# MDM_V3_ControlBoard_A.net
KiCad netlist of a schematic drawn in EAGLE
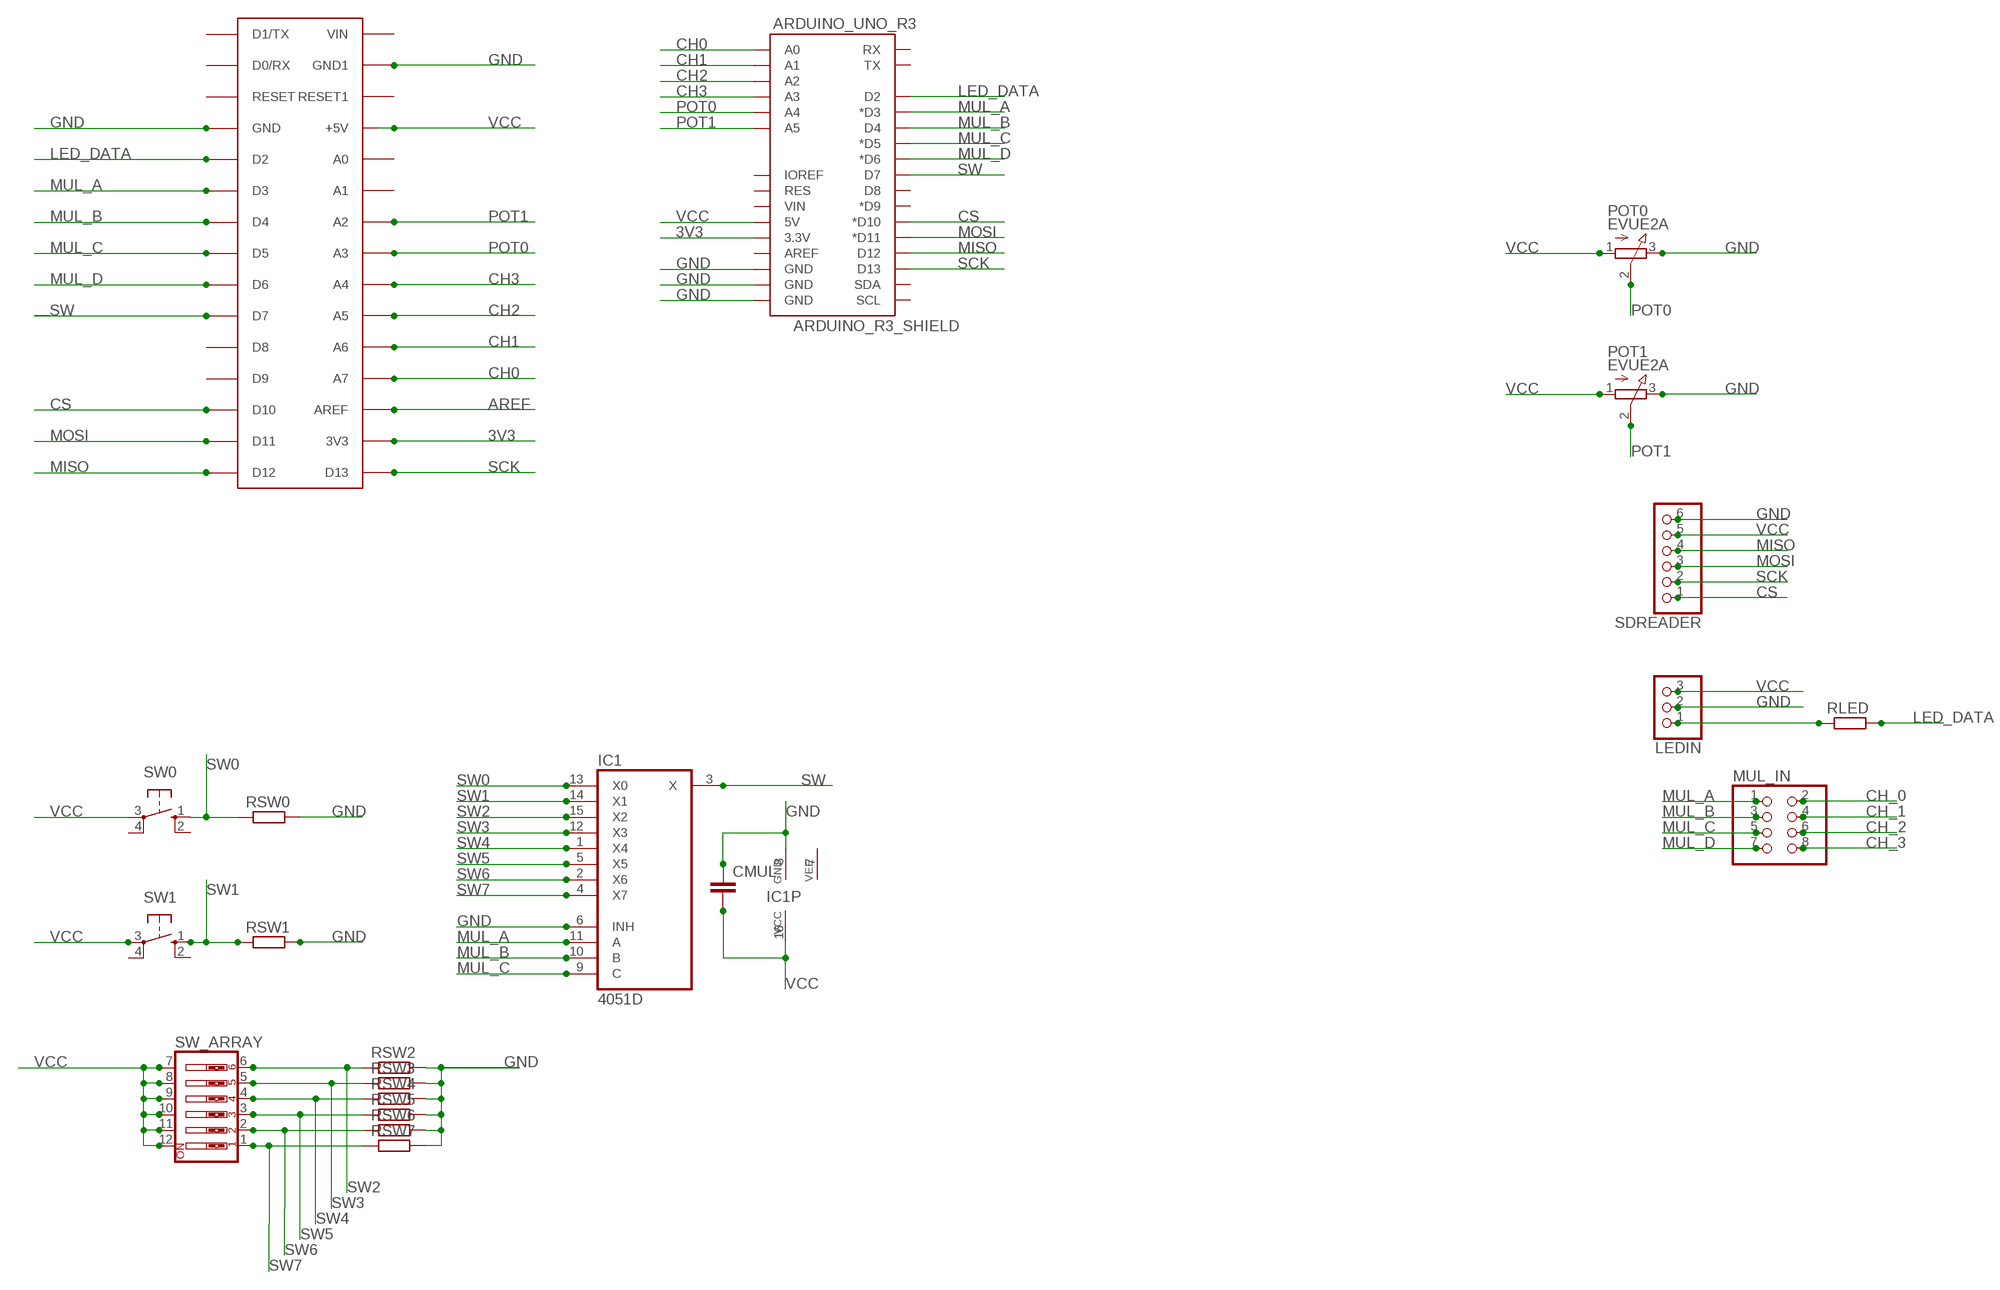
[diagram p0: schematic, sheet 1]

(export (version "E")
  (design (tool "Eeschema 10.0.6"))
  (components
    (comp (ref "ARDUINO_NANO")
      (value "ARDUINONANO")
      (footprint "eagle-import:PDIP-32")
      (libsource (lib "eagle-import") (part "ARDUINONANO"))
    )
    (comp (ref "ARDUINO_UNO_R3")
      (value "ARDUINO_R3_SHIELD")
      (footprint "eagle-import:UNO_R3_SHIELD")
      (libsource (lib "eagle-import") (part "ARDUINO_R3_SHIELD"))
    )
    (comp (ref "CMUL")
      (value "C-EUC1206")
      (footprint "eagle-import:C1206")
      (libsource (lib "eagle-import") (part "C-EUC1206"))
    )
    (comp (ref "IC1")
      (value "4051D")
      (footprint "eagle-import:SO16")
      (libsource (lib "eagle-import") (part "4051D"))
    )
    (comp (ref "LEDIN")
      (value "PINHD-1X3")
      (footprint "eagle-import:1X03")
      (libsource (lib "eagle-import") (part "PINHD-1X3"))
    )
    (comp (ref "MUL_IN")
      (value "PINHD-2X4")
      (footprint "eagle-import:2X04")
      (libsource (lib "eagle-import") (part "PINHD-2X4"))
    )
    (comp (ref "POT0")
      (value "EVUE2A")
      (footprint "eagle-import:EVUE")
      (libsource (lib "eagle-import") (part "EVUE2A"))
    )
    (comp (ref "POT1")
      (value "EVUE2A")
      (footprint "eagle-import:EVUE")
      (libsource (lib "eagle-import") (part "EVUE2A"))
    )
    (comp (ref "RLED")
      (value "R-EU_M1206")
      (footprint "eagle-import:M1206")
      (libsource (lib "eagle-import") (part "R-EU_M1206"))
    )
    (comp (ref "RSW0")
      (value "R-EU_M1206")
      (footprint "eagle-import:M1206")
      (libsource (lib "eagle-import") (part "R-EU_M1206"))
    )
    (comp (ref "RSW1")
      (value "R-EU_M1206")
      (footprint "eagle-import:M1206")
      (libsource (lib "eagle-import") (part "R-EU_M1206"))
    )
    (comp (ref "RSW2")
      (value "R-EU_M1206")
      (footprint "eagle-import:M1206")
      (libsource (lib "eagle-import") (part "R-EU_M1206"))
    )
    (comp (ref "RSW3")
      (value "R-EU_M1206")
      (footprint "eagle-import:M1206")
      (libsource (lib "eagle-import") (part "R-EU_M1206"))
    )
    (comp (ref "RSW4")
      (value "R-EU_M1206")
      (footprint "eagle-import:M1206")
      (libsource (lib "eagle-import") (part "R-EU_M1206"))
    )
    (comp (ref "RSW5")
      (value "R-EU_M1206")
      (footprint "eagle-import:M1206")
      (libsource (lib "eagle-import") (part "R-EU_M1206"))
    )
    (comp (ref "RSW6")
      (value "R-EU_M1206")
      (footprint "eagle-import:M1206")
      (libsource (lib "eagle-import") (part "R-EU_M1206"))
    )
    (comp (ref "RSW7")
      (value "R-EU_M1206")
      (footprint "eagle-import:M1206")
      (libsource (lib "eagle-import") (part "R-EU_M1206"))
    )
    (comp (ref "SDREADER")
      (value "PINHD-1X6")
      (footprint "eagle-import:1X06")
      (libsource (lib "eagle-import") (part "PINHD-1X6"))
    )
    (comp (ref "SW0")
      (value "10-XX")
      (footprint "eagle-import:B3F-10XX")
      (fields (field (name "MPN") "B3F-1000"))
      (libsource (lib "eagle-import") (part "10-XX"))
    )
    (comp (ref "SW1")
      (value "10-XX")
      (footprint "eagle-import:B3F-10XX")
      (fields (field (name "MPN") "B3F-1000"))
      (libsource (lib "eagle-import") (part "10-XX"))
    )
    (comp (ref "SW_ARRAY")
      (value "SW_DIP-6")
      (footprint "eagle-import:EDG-06")
      (libsource (lib "eagle-import") (part "SW_DIP-6"))
    )
  )
  (nets
    (net (code "1") (name "/3V3") (class "Default")
      (node (ref "ARDUINO_NANO") (pin "3V3") (pinfunction "3V3_3V3") (pintype "bidirectional"))
      (node (ref "ARDUINO_UNO_R3") (pin "3.3V") (pinfunction "3.3V_3.3V") (pintype "bidirectional"))
    )
    (net (code "2") (name "/AREF") (class "Default")
      (node (ref "ARDUINO_NANO") (pin "AREF") (pinfunction "AREF_AREF") (pintype "bidirectional"))
    )
    (net (code "3") (name "/CH0") (class "Default")
      (node (ref "ARDUINO_NANO") (pin "A7") (pinfunction "A7_A7") (pintype "bidirectional"))
      (node (ref "ARDUINO_UNO_R3") (pin "A0") (pinfunction "A0_A0") (pintype "bidirectional"))
    )
    (net (code "4") (name "/CH1") (class "Default")
      (node (ref "ARDUINO_NANO") (pin "A6") (pinfunction "A6_A6") (pintype "bidirectional"))
      (node (ref "ARDUINO_UNO_R3") (pin "A1") (pinfunction "A1_A1") (pintype "bidirectional"))
    )
    (net (code "5") (name "/CH2") (class "Default")
      (node (ref "ARDUINO_NANO") (pin "A5") (pinfunction "A5_A5") (pintype "bidirectional"))
      (node (ref "ARDUINO_UNO_R3") (pin "A2") (pinfunction "A2_A2") (pintype "bidirectional"))
    )
    (net (code "6") (name "/CH3") (class "Default")
      (node (ref "ARDUINO_NANO") (pin "A4") (pinfunction "A4_A4") (pintype "bidirectional"))
      (node (ref "ARDUINO_UNO_R3") (pin "A3") (pinfunction "A3_A3") (pintype "bidirectional"))
    )
    (net (code "7") (name "/CH_0") (class "Default")
      (node (ref "MUL_IN") (pin "2") (pinfunction "2_2") (pintype "passive"))
    )
    (net (code "8") (name "/CH_1") (class "Default")
      (node (ref "MUL_IN") (pin "4") (pinfunction "4_4") (pintype "passive"))
    )
    (net (code "9") (name "/CH_2") (class "Default")
      (node (ref "MUL_IN") (pin "6") (pinfunction "6_6") (pintype "passive"))
    )
    (net (code "10") (name "/CH_3") (class "Default")
      (node (ref "MUL_IN") (pin "8") (pinfunction "8_8") (pintype "passive"))
    )
    (net (code "11") (name "/CS") (class "Default")
      (node (ref "ARDUINO_NANO") (pin "D10") (pinfunction "D10_D10") (pintype "bidirectional"))
      (node (ref "ARDUINO_UNO_R3") (pin "D10") (pinfunction "*D10_D10") (pintype "bidirectional"))
      (node (ref "SDREADER") (pin "1") (pinfunction "1_1") (pintype "passive"))
    )
    (net (code "12") (name "/GND") (class "Default")
      (node (ref "ARDUINO_NANO") (pin "GND") (pinfunction "GND_GND") (pintype "bidirectional"))
      (node (ref "ARDUINO_NANO") (pin "GND1") (pinfunction "GND1_GND1") (pintype "bidirectional"))
      (node (ref "ARDUINO_UNO_R3") (pin "GND@0") (pinfunction "GND_GND@0") (pintype "bidirectional"))
      (node (ref "ARDUINO_UNO_R3") (pin "GND@1") (pinfunction "GND_GND@1") (pintype "bidirectional"))
      (node (ref "ARDUINO_UNO_R3") (pin "GND@2") (pinfunction "GND_GND@2") (pintype "bidirectional"))
      (node (ref "CMUL") (pin "1") (pinfunction "1_1") (pintype "passive"))
      (node (ref "IC1") (pin "6") (pinfunction "INH_6") (pintype "input"))
      (node (ref "IC1") (pin "8") (pinfunction "GND_8") (pintype "power_in"))
      (node (ref "LEDIN") (pin "2") (pinfunction "2_2") (pintype "passive"))
      (node (ref "POT0") (pin "3") (pinfunction "E_3") (pintype "passive"))
      (node (ref "POT1") (pin "3") (pinfunction "E_3") (pintype "passive"))
      (node (ref "RSW0") (pin "2") (pinfunction "2_2") (pintype "passive"))
      (node (ref "RSW1") (pin "2") (pinfunction "2_2") (pintype "passive"))
      (node (ref "RSW2") (pin "2") (pinfunction "2_2") (pintype "passive"))
      (node (ref "RSW3") (pin "2") (pinfunction "2_2") (pintype "passive"))
      (node (ref "RSW4") (pin "2") (pinfunction "2_2") (pintype "passive"))
      (node (ref "RSW5") (pin "2") (pinfunction "2_2") (pintype "passive"))
      (node (ref "RSW6") (pin "2") (pinfunction "2_2") (pintype "passive"))
      (node (ref "RSW7") (pin "2") (pinfunction "2_2") (pintype "passive"))
      (node (ref "SDREADER") (pin "6") (pinfunction "6_6") (pintype "passive"))
    )
    (net (code "13") (name "/LED_DATA") (class "Default")
      (node (ref "ARDUINO_NANO") (pin "D2") (pinfunction "D2_D2") (pintype "bidirectional"))
      (node (ref "ARDUINO_UNO_R3") (pin "D2") (pinfunction "D2_D2") (pintype "bidirectional"))
      (node (ref "RLED") (pin "2") (pinfunction "2_2") (pintype "passive"))
    )
    (net (code "14") (name "/MISO") (class "Default")
      (node (ref "ARDUINO_NANO") (pin "D12") (pinfunction "D12_D12") (pintype "bidirectional"))
      (node (ref "ARDUINO_UNO_R3") (pin "D12") (pinfunction "D12_D12") (pintype "bidirectional"))
      (node (ref "SDREADER") (pin "4") (pinfunction "4_4") (pintype "passive"))
    )
    (net (code "15") (name "/MOSI") (class "Default")
      (node (ref "ARDUINO_NANO") (pin "D11") (pinfunction "D11_D11") (pintype "bidirectional"))
      (node (ref "ARDUINO_UNO_R3") (pin "D11") (pinfunction "*D11_D11") (pintype "bidirectional"))
      (node (ref "SDREADER") (pin "3") (pinfunction "3_3") (pintype "passive"))
    )
    (net (code "16") (name "/MUL_A") (class "Default")
      (node (ref "ARDUINO_NANO") (pin "D3") (pinfunction "D3_D3") (pintype "bidirectional"))
      (node (ref "ARDUINO_UNO_R3") (pin "D3") (pinfunction "*D3_D3") (pintype "bidirectional"))
      (node (ref "IC1") (pin "11") (pinfunction "A_11") (pintype "input"))
      (node (ref "MUL_IN") (pin "1") (pinfunction "1_1") (pintype "passive"))
    )
    (net (code "17") (name "/MUL_B") (class "Default")
      (node (ref "ARDUINO_NANO") (pin "D4") (pinfunction "D4_D4") (pintype "bidirectional"))
      (node (ref "ARDUINO_UNO_R3") (pin "D4") (pinfunction "D4_D4") (pintype "bidirectional"))
      (node (ref "IC1") (pin "10") (pinfunction "B_10") (pintype "input"))
      (node (ref "MUL_IN") (pin "3") (pinfunction "3_3") (pintype "passive"))
    )
    (net (code "18") (name "/MUL_C") (class "Default")
      (node (ref "ARDUINO_NANO") (pin "D5") (pinfunction "D5_D5") (pintype "bidirectional"))
      (node (ref "ARDUINO_UNO_R3") (pin "D5") (pinfunction "*D5_D5") (pintype "bidirectional"))
      (node (ref "IC1") (pin "9") (pinfunction "C_9") (pintype "input"))
      (node (ref "MUL_IN") (pin "5") (pinfunction "5_5") (pintype "passive"))
    )
    (net (code "19") (name "/MUL_D") (class "Default")
      (node (ref "ARDUINO_NANO") (pin "D6") (pinfunction "D6_D6") (pintype "bidirectional"))
      (node (ref "ARDUINO_UNO_R3") (pin "D6") (pinfunction "*D6_D6") (pintype "bidirectional"))
      (node (ref "MUL_IN") (pin "7") (pinfunction "7_7") (pintype "passive"))
    )
    (net (code "20") (name "/POT0") (class "Default")
      (node (ref "ARDUINO_NANO") (pin "A3") (pinfunction "A3_A3") (pintype "bidirectional"))
      (node (ref "ARDUINO_UNO_R3") (pin "A4") (pinfunction "A4_A4") (pintype "bidirectional"))
      (node (ref "POT0") (pin "2") (pinfunction "S_2") (pintype "passive"))
    )
    (net (code "21") (name "/POT1") (class "Default")
      (node (ref "ARDUINO_NANO") (pin "A2") (pinfunction "A2_A2") (pintype "bidirectional"))
      (node (ref "ARDUINO_UNO_R3") (pin "A5") (pinfunction "A5_A5") (pintype "bidirectional"))
      (node (ref "POT1") (pin "2") (pinfunction "S_2") (pintype "passive"))
    )
    (net (code "22") (name "/SCK") (class "Default")
      (node (ref "ARDUINO_NANO") (pin "D13") (pinfunction "D13_D13") (pintype "bidirectional"))
      (node (ref "ARDUINO_UNO_R3") (pin "D13") (pinfunction "D13_D13") (pintype "bidirectional"))
      (node (ref "SDREADER") (pin "2") (pinfunction "2_2") (pintype "passive"))
    )
    (net (code "23") (name "/SW") (class "Default")
      (node (ref "ARDUINO_NANO") (pin "D7") (pinfunction "D7_D7") (pintype "bidirectional"))
      (node (ref "ARDUINO_UNO_R3") (pin "D7") (pinfunction "D7_D7") (pintype "bidirectional"))
      (node (ref "IC1") (pin "3") (pinfunction "X_3") (pintype "bidirectional"))
    )
    (net (code "24") (name "/SW0") (class "Default")
      (node (ref "IC1") (pin "13") (pinfunction "X0_13") (pintype "bidirectional"))
      (node (ref "RSW0") (pin "1") (pinfunction "1_1") (pintype "passive"))
      (node (ref "SW0") (pin "1") (pinfunction "S_1") (pintype "passive"))
    )
    (net (code "25") (name "/SW1") (class "Default")
      (node (ref "IC1") (pin "14") (pinfunction "X1_14") (pintype "bidirectional"))
      (node (ref "RSW1") (pin "1") (pinfunction "1_1") (pintype "passive"))
      (node (ref "SW1") (pin "1") (pinfunction "S_1") (pintype "passive"))
    )
    (net (code "26") (name "/SW2") (class "Default")
      (node (ref "IC1") (pin "15") (pinfunction "X2_15") (pintype "bidirectional"))
      (node (ref "RSW2") (pin "1") (pinfunction "1_1") (pintype "passive"))
      (node (ref "SW_ARRAY") (pin "6") (pinfunction "6_6") (pintype "passive"))
    )
    (net (code "27") (name "/SW3") (class "Default")
      (node (ref "IC1") (pin "12") (pinfunction "X3_12") (pintype "bidirectional"))
      (node (ref "RSW3") (pin "1") (pinfunction "1_1") (pintype "passive"))
      (node (ref "SW_ARRAY") (pin "5") (pinfunction "5_5") (pintype "passive"))
    )
    (net (code "28") (name "/SW4") (class "Default")
      (node (ref "IC1") (pin "1") (pinfunction "X4_1") (pintype "bidirectional"))
      (node (ref "RSW4") (pin "1") (pinfunction "1_1") (pintype "passive"))
      (node (ref "SW_ARRAY") (pin "4") (pinfunction "4_4") (pintype "passive"))
    )
    (net (code "29") (name "/SW5") (class "Default")
      (node (ref "IC1") (pin "5") (pinfunction "X5_5") (pintype "bidirectional"))
      (node (ref "RSW5") (pin "1") (pinfunction "1_1") (pintype "passive"))
      (node (ref "SW_ARRAY") (pin "3") (pinfunction "3_3") (pintype "passive"))
    )
    (net (code "30") (name "/SW6") (class "Default")
      (node (ref "IC1") (pin "2") (pinfunction "X6_2") (pintype "bidirectional"))
      (node (ref "RSW6") (pin "1") (pinfunction "1_1") (pintype "passive"))
      (node (ref "SW_ARRAY") (pin "2") (pinfunction "2_2") (pintype "passive"))
    )
    (net (code "31") (name "/SW7") (class "Default")
      (node (ref "IC1") (pin "4") (pinfunction "X7_4") (pintype "bidirectional"))
      (node (ref "RSW7") (pin "1") (pinfunction "1_1") (pintype "passive"))
      (node (ref "SW_ARRAY") (pin "1") (pinfunction "1_1") (pintype "passive"))
    )
    (net (code "32") (name "/VCC") (class "Default")
      (node (ref "ARDUINO_NANO") (pin "+5V") (pinfunction "+5V_+5V") (pintype "bidirectional"))
      (node (ref "ARDUINO_UNO_R3") (pin "5V") (pinfunction "5V_5V") (pintype "bidirectional"))
      (node (ref "CMUL") (pin "2") (pinfunction "2_2") (pintype "passive"))
      (node (ref "IC1") (pin "16") (pinfunction "VCC_16") (pintype "power_in"))
      (node (ref "LEDIN") (pin "3") (pinfunction "3_3") (pintype "passive"))
      (node (ref "POT0") (pin "1") (pinfunction "A_1") (pintype "passive"))
      (node (ref "POT1") (pin "1") (pinfunction "A_1") (pintype "passive"))
      (node (ref "SDREADER") (pin "5") (pinfunction "5_5") (pintype "passive"))
      (node (ref "SW0") (pin "3") (pinfunction "P_3") (pintype "passive"))
      (node (ref "SW1") (pin "3") (pinfunction "P_3") (pintype "passive"))
      (node (ref "SW_ARRAY") (pin "10") (pinfunction "10_10") (pintype "passive"))
      (node (ref "SW_ARRAY") (pin "11") (pinfunction "11_11") (pintype "passive"))
      (node (ref "SW_ARRAY") (pin "12") (pinfunction "12_12") (pintype "passive"))
      (node (ref "SW_ARRAY") (pin "7") (pinfunction "7_7") (pintype "passive"))
      (node (ref "SW_ARRAY") (pin "8") (pinfunction "8_8") (pintype "passive"))
      (node (ref "SW_ARRAY") (pin "9") (pinfunction "9_9") (pintype "passive"))
    )
    (net (code "33") (name "/VEE") (class "Default")
      (node (ref "IC1") (pin "7") (pinfunction "VEE_7") (pintype "power_in"))
    )
    (net (code "34") (name "Net-(LEDIN-Pad1)") (class "Default")
      (node (ref "LEDIN") (pin "1") (pinfunction "1_1") (pintype "passive"))
      (node (ref "RLED") (pin "1") (pinfunction "1_1") (pintype "passive"))
    )
    (net (code "35") (name "unconnected-(ARDUINO_NANO-PadA0)") (class "Default")
      (node (ref "ARDUINO_NANO") (pin "A0") (pinfunction "A0_A0") (pintype "bidirectional"))
    )
    (net (code "36") (name "unconnected-(ARDUINO_NANO-PadA1)") (class "Default")
      (node (ref "ARDUINO_NANO") (pin "A1") (pinfunction "A1_A1") (pintype "bidirectional"))
    )
    (net (code "37") (name "unconnected-(ARDUINO_NANO-PadD0{slash}RX)") (class "Default")
      (node (ref "ARDUINO_NANO") (pin "D0/RX") (pinfunction "D0/RX_D0/RX") (pintype "bidirectional"))
    )
    (net (code "38") (name "unconnected-(ARDUINO_NANO-PadD1{slash}TX)") (class "Default")
      (node (ref "ARDUINO_NANO") (pin "D1/TX") (pinfunction "D1/TX_D1/TX") (pintype "bidirectional"))
    )
    (net (code "39") (name "unconnected-(ARDUINO_NANO-PadD8)") (class "Default")
      (node (ref "ARDUINO_NANO") (pin "D8") (pinfunction "D8_D8") (pintype "bidirectional"))
    )
    (net (code "40") (name "unconnected-(ARDUINO_NANO-PadD9)") (class "Default")
      (node (ref "ARDUINO_NANO") (pin "D9") (pinfunction "D9_D9") (pintype "bidirectional"))
    )
    (net (code "41") (name "unconnected-(ARDUINO_NANO-PadRESET)") (class "Default")
      (node (ref "ARDUINO_NANO") (pin "RESET") (pinfunction "RESET_RESET") (pintype "bidirectional"))
    )
    (net (code "42") (name "unconnected-(ARDUINO_NANO-PadRESET1)") (class "Default")
      (node (ref "ARDUINO_NANO") (pin "RESET1") (pinfunction "RESET1_RESET1") (pintype "bidirectional"))
    )
    (net (code "43") (name "unconnected-(ARDUINO_NANO-PadVIN)") (class "Default")
      (node (ref "ARDUINO_NANO") (pin "VIN") (pinfunction "VIN_VIN") (pintype "bidirectional"))
    )
    (net (code "44") (name "unconnected-(ARDUINO_UNO_R3-*D9-PadD9)") (class "Default")
      (node (ref "ARDUINO_UNO_R3") (pin "D9") (pinfunction "*D9_D9") (pintype "bidirectional"))
    )
    (net (code "45") (name "unconnected-(ARDUINO_UNO_R3-PadAREF)") (class "Default")
      (node (ref "ARDUINO_UNO_R3") (pin "AREF") (pinfunction "AREF_AREF") (pintype "bidirectional"))
    )
    (net (code "46") (name "unconnected-(ARDUINO_UNO_R3-PadD8)") (class "Default")
      (node (ref "ARDUINO_UNO_R3") (pin "D8") (pinfunction "D8_D8") (pintype "bidirectional"))
    )
    (net (code "47") (name "unconnected-(ARDUINO_UNO_R3-PadIOREF)") (class "Default")
      (node (ref "ARDUINO_UNO_R3") (pin "IOREF") (pinfunction "IOREF_IOREF") (pintype "bidirectional"))
    )
    (net (code "48") (name "unconnected-(ARDUINO_UNO_R3-PadRES)") (class "Default")
      (node (ref "ARDUINO_UNO_R3") (pin "RES") (pinfunction "RES_RES") (pintype "bidirectional"))
    )
    (net (code "49") (name "unconnected-(ARDUINO_UNO_R3-PadRX)") (class "Default")
      (node (ref "ARDUINO_UNO_R3") (pin "RX") (pinfunction "RX_RX") (pintype "bidirectional"))
    )
    (net (code "50") (name "unconnected-(ARDUINO_UNO_R3-PadSCL)") (class "Default")
      (node (ref "ARDUINO_UNO_R3") (pin "SCL") (pinfunction "SCL_SCL") (pintype "bidirectional"))
    )
    (net (code "51") (name "unconnected-(ARDUINO_UNO_R3-PadSDA)") (class "Default")
      (node (ref "ARDUINO_UNO_R3") (pin "SDA") (pinfunction "SDA_SDA") (pintype "bidirectional"))
    )
    (net (code "52") (name "unconnected-(ARDUINO_UNO_R3-PadTX)") (class "Default")
      (node (ref "ARDUINO_UNO_R3") (pin "TX") (pinfunction "TX_TX") (pintype "bidirectional"))
    )
    (net (code "53") (name "unconnected-(ARDUINO_UNO_R3-PadVIN)") (class "Default")
      (node (ref "ARDUINO_UNO_R3") (pin "VIN") (pinfunction "VIN_VIN") (pintype "bidirectional"))
    )
    (net (code "54") (name "unconnected-(SW0-P1-Pad4)") (class "Default")
      (node (ref "SW0") (pin "4") (pinfunction "P1_4") (pintype "passive"))
    )
    (net (code "55") (name "unconnected-(SW0-S1-Pad2)") (class "Default")
      (node (ref "SW0") (pin "2") (pinfunction "S1_2") (pintype "passive"))
    )
    (net (code "56") (name "unconnected-(SW1-P1-Pad4)") (class "Default")
      (node (ref "SW1") (pin "4") (pinfunction "P1_4") (pintype "passive"))
    )
    (net (code "57") (name "unconnected-(SW1-S1-Pad2)") (class "Default")
      (node (ref "SW1") (pin "2") (pinfunction "S1_2") (pintype "passive"))
    )
  )
)
